# MITCH_2021-0_SHIELD.net
KiCad netlist of a schematic drawn in EAGLE
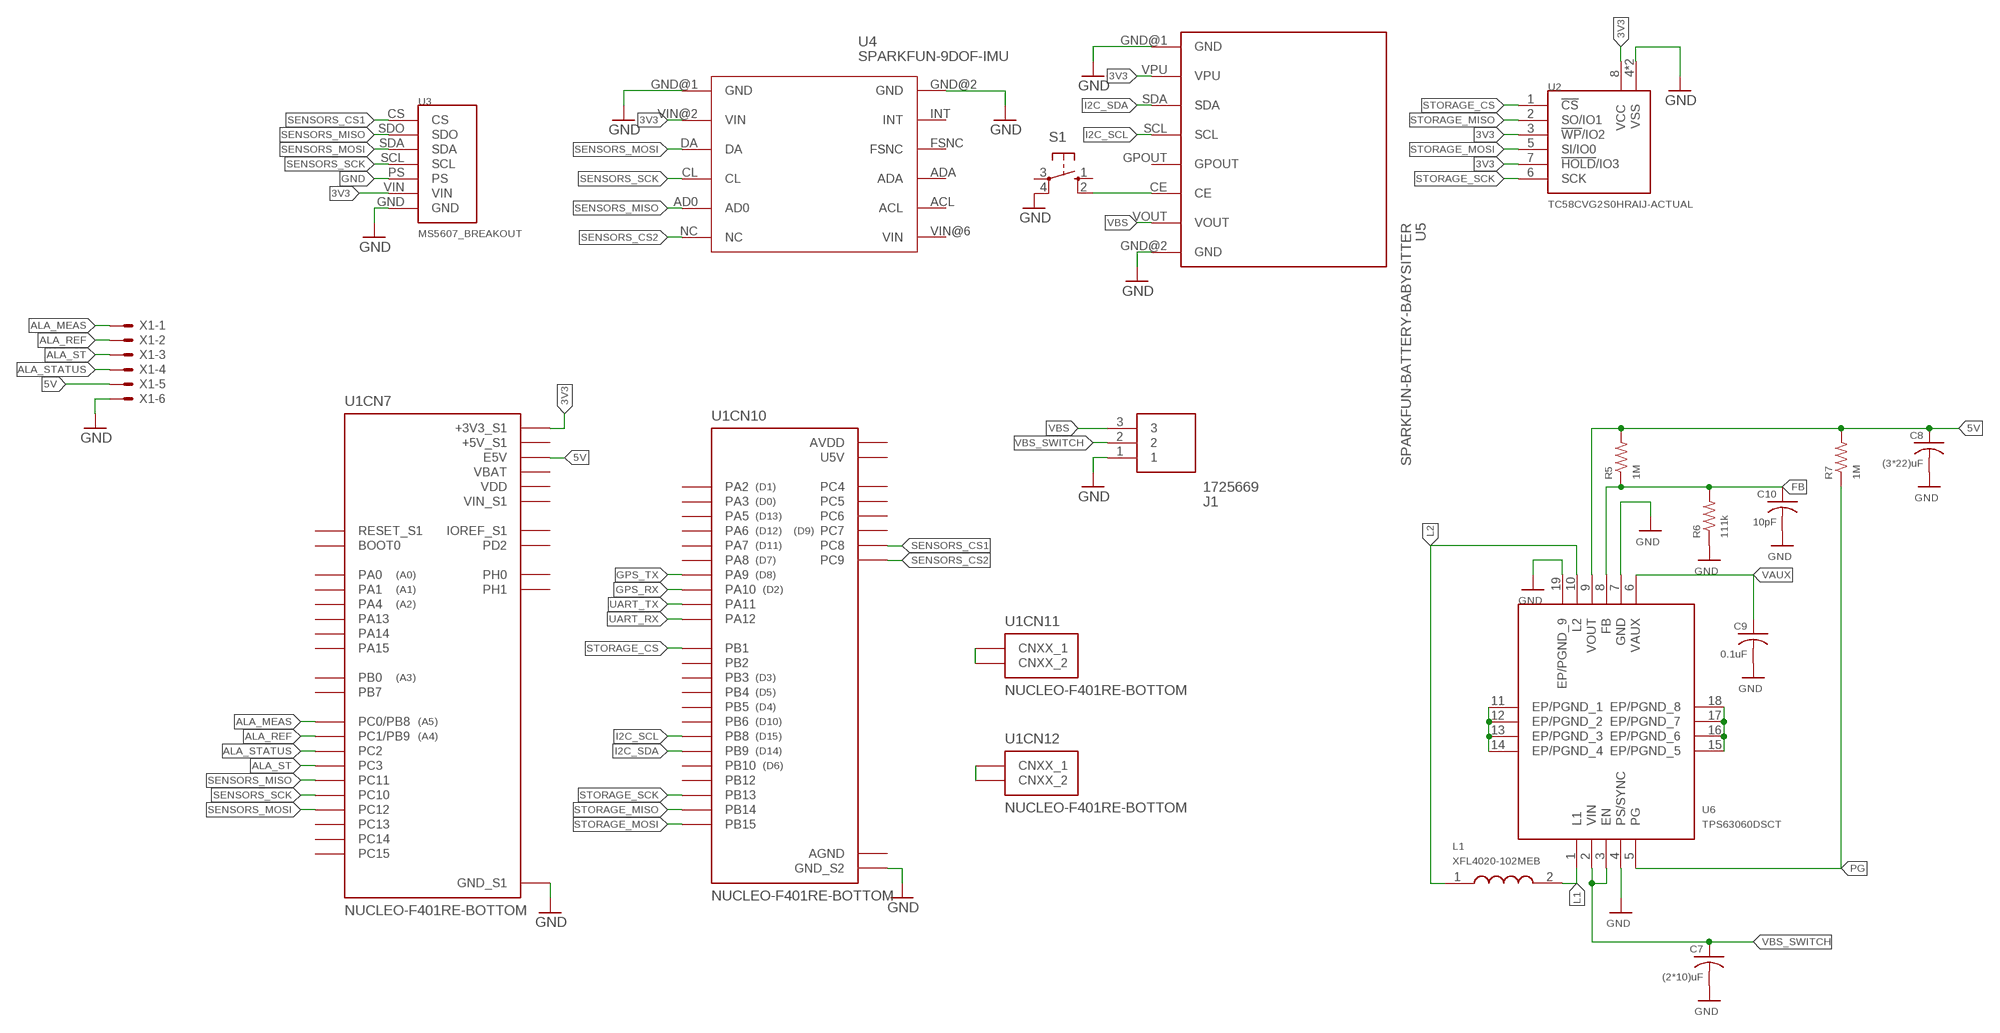
[diagram p0: schematic, sheet 1]

(export (version "E")
  (design (tool "Eeschema 10.0.6"))
  (components
    (comp (ref "C7")
      (value "(2*10)uF")
      (footprint "eagle-import:C0805")
      (libsource (lib "eagle-import") (part "C-USC0805"))
    )
    (comp (ref "C8")
      (value "(3*22)uF")
      (footprint "eagle-import:C0805")
      (libsource (lib "eagle-import") (part "C-USC0805"))
    )
    (comp (ref "C9")
      (value "0.1uF")
      (footprint "eagle-import:C0805")
      (libsource (lib "eagle-import") (part "C-USC0805"))
    )
    (comp (ref "C10")
      (value "10pF")
      (footprint "eagle-import:C0805")
      (libsource (lib "eagle-import") (part "C-USC0805"))
    )
    (comp (ref "J1")
      (value "1725669")
      (footprint "eagle-import:1725669")
      (fields (field (name "MOUSER_PART_NUMBER") "651-1725669"))
      (libsource (lib "eagle-import") (part "1725669"))
    )
    (comp (ref "L1")
      (value "XFL4020-102MEB")
      (footprint "eagle-import:XFL4020102MEB")
      (fields (field (name "MOUSER_PART_NUMBER") "994-XFL4020-102MEB"))
      (libsource (lib "eagle-import") (part "XFL4020-102MEB"))
    )
    (comp (ref "R5")
      (value "1M")
      (footprint "eagle-import:R0805")
      (libsource (lib "eagle-import") (part "R-US_R0805"))
    )
    (comp (ref "R6")
      (value "111k")
      (footprint "eagle-import:R0805")
      (libsource (lib "eagle-import") (part "R-US_R0805"))
    )
    (comp (ref "R7")
      (value "1M")
      (footprint "eagle-import:R0805")
      (libsource (lib "eagle-import") (part "R-US_R0805"))
    )
    (comp (ref "S1")
      (value "10-XX")
      (footprint "eagle-import:B3F-10XX")
      (fields (field (name "MPN") "B3F-1000"))
      (libsource (lib "eagle-import") (part "10-XX"))
    )
    (comp (ref "U1")
      (value "NUCLEO-F401RE-BOTTOM")
      (footprint "eagle-import:ST_NUCLEO-F401RE_BOTTOM")
      (fields (field (name "MF") "STMicroelectronics") (field (name "MP") "NUCLEO-F401RE"))
      (libsource (lib "eagle-import") (part "NUCLEO-F401RE-BOTTOM"))
    )
    (comp (ref "U2")
      (value "TC58CVG2S0HRAIJ-ACTUAL")
      (footprint "eagle-import:COMPUTER2_SON127P800X600X80-9T350X440N")
      (libsource (lib "eagle-import") (part "TC58CVG2S0HRAIJ-ACTUAL"))
    )
    (comp (ref "U3")
      (value "MS5607_BREAKOUT")
      (footprint "eagle-import:MS5607_BREAKOUT")
      (libsource (lib "eagle-import") (part "MS5607_BREAKOUT"))
    )
    (comp (ref "U4")
      (value "SPARKFUN-9DOF-IMU")
      (footprint "eagle-import:SPARKFUN-9DOF-IMU1")
      (libsource (lib "eagle-import") (part "SPARKFUN-9DOF-IMU"))
    )
    (comp (ref "U5")
      (value "SPARKFUN-BATTERY-BABYSITTER")
      (footprint "eagle-import:SPARKFUN-BATTERY-BABYSITTER")
      (libsource (lib "eagle-import") (part "SPARKFUN-BATTERY-BABYSITTER"))
    )
    (comp (ref "U6")
      (value "TPS63060DSCT")
      (footprint "eagle-import:TPS63060DSCT")
      (fields (field (name "MOUSER_PART_NUMBER") "595-TPS63060DSCT"))
      (libsource (lib "eagle-import") (part "TPS63060DSCT"))
    )
    (comp (ref "X1")
      (value "22-23-2061")
      (footprint "eagle-import:22-23-2061")
      (fields (field (name "MF") "MOLEX"))
      (libsource (lib "eagle-import") (part "22-23-2061"))
    )
  )
  (nets
    (net (code "1") (name "/+5V_S1") (class "Default")
      (node (ref "U1") (pin "CN7_18") (pinfunction "+5V_S1_CN7_18") (pintype "power_in"))
    )
    (net (code "2") (name "/AGND") (class "Default")
      (node (ref "U1") (pin "CN10_32") (pinfunction "AGND_CN10_32") (pintype "power_in"))
    )
    (net (code "3") (name "/AVDD") (class "Default")
      (node (ref "U1") (pin "CN10_7") (pinfunction "AVDD_CN10_7") (pintype "power_in"))
    )
    (net (code "4") (name "/U5V") (class "Default")
      (node (ref "U1") (pin "CN10_8") (pinfunction "U5V_CN10_8") (pintype "power_in"))
    )
    (net (code "5") (name "/VBAT") (class "Default")
      (node (ref "U1") (pin "CN7_33") (pinfunction "VBAT_CN7_33") (pintype "power_in"))
    )
    (net (code "6") (name "/VDD") (class "Default")
      (node (ref "U1") (pin "CN7_5") (pinfunction "VDD_CN7_5") (pintype "power_in"))
    )
    (net (code "7") (name "/VIN_S1") (class "Default")
      (node (ref "U1") (pin "CN7_24") (pinfunction "VIN_S1_CN7_24") (pintype "power_in"))
    )
    (net (code "8") (name "3V3") (class "Default")
      (node (ref "U1") (pin "CN7_16") (pinfunction "+3V3_S1_CN7_16") (pintype "power_in"))
      (node (ref "U2") (pin "3") (pinfunction "~{WP}/IO2_3") (pintype "bidirectional"))
      (node (ref "U2") (pin "7") (pinfunction "~{HOLD}/IO3_7") (pintype "bidirectional"))
      (node (ref "U2") (pin "8") (pinfunction "VCC_8") (pintype "bidirectional"))
      (node (ref "U3") (pin "VIN") (pinfunction "VIN_VIN") (pintype "bidirectional"))
      (node (ref "U4") (pin "VIN@2") (pinfunction "VIN_VIN@2") (pintype "bidirectional"))
      (node (ref "U5") (pin "VPU") (pinfunction "VPU_VPU") (pintype "bidirectional"))
    )
    (net (code "9") (name "5V") (class "Default")
      (node (ref "C8") (pin "1") (pinfunction "1_1") (pintype "passive"))
      (node (ref "R5") (pin "2") (pinfunction "2_2") (pintype "passive"))
      (node (ref "R7") (pin "2") (pinfunction "2_2") (pintype "passive"))
      (node (ref "U1") (pin "CN7_6") (pinfunction "E5V_CN7_6") (pintype "power_in"))
      (node (ref "U6") (pin "9") (pinfunction "VOUT_9") (pintype "bidirectional"))
      (node (ref "X1") (pin "5") (pinfunction "S_5") (pintype "passive"))
    )
    (net (code "10") (name "ALA_MEAS") (class "Default")
      (node (ref "U1") (pin "CN7_38") (pinfunction "PC0/PB8_CN7_38") (pintype "bidirectional"))
      (node (ref "X1") (pin "1") (pinfunction "S_1") (pintype "passive"))
    )
    (net (code "11") (name "ALA_REF") (class "Default")
      (node (ref "U1") (pin "CN7_36") (pinfunction "PC1/PB9_CN7_36") (pintype "bidirectional"))
      (node (ref "X1") (pin "2") (pinfunction "S_2") (pintype "passive"))
    )
    (net (code "12") (name "ALA_ST") (class "Default")
      (node (ref "U1") (pin "CN7_37") (pinfunction "PC3_CN7_37") (pintype "bidirectional"))
      (node (ref "X1") (pin "3") (pinfunction "S_3") (pintype "passive"))
    )
    (net (code "13") (name "ALA_STATUS") (class "Default")
      (node (ref "U1") (pin "CN7_35") (pinfunction "PC2_CN7_35") (pintype "bidirectional"))
      (node (ref "X1") (pin "4") (pinfunction "S_4") (pintype "passive"))
    )
    (net (code "14") (name "FB") (class "Default")
      (node (ref "C10") (pin "1") (pinfunction "1_1") (pintype "passive"))
      (node (ref "R5") (pin "1") (pinfunction "1_1") (pintype "passive"))
      (node (ref "R6") (pin "2") (pinfunction "2_2") (pintype "passive"))
      (node (ref "U6") (pin "8") (pinfunction "FB_8") (pintype "bidirectional"))
    )
    (net (code "15") (name "GND") (class "Default")
      (node (ref "C10") (pin "2") (pinfunction "2_2") (pintype "passive"))
      (node (ref "C7") (pin "2") (pinfunction "2_2") (pintype "passive"))
      (node (ref "C8") (pin "2") (pinfunction "2_2") (pintype "passive"))
      (node (ref "C9") (pin "2") (pinfunction "2_2") (pintype "passive"))
      (node (ref "J1") (pin "1") (pinfunction "1_1") (pintype "bidirectional"))
      (node (ref "R6") (pin "1") (pinfunction "1_1") (pintype "passive"))
      (node (ref "S1") (pin "4") (pinfunction "P1_4") (pintype "passive"))
      (node (ref "U1") (pin "CN10_20") (pinfunction "GND_S2_CN10_20") (pintype "power_in"))
      (node (ref "U1") (pin "CN10_9") (pinfunction "GND_S2_CN10_9") (pintype "power_in"))
      (node (ref "U1") (pin "CN7_19") (pinfunction "GND_S1_CN7_19") (pintype "power_in"))
      (node (ref "U1") (pin "CN7_20") (pinfunction "GND_S1_CN7_20") (pintype "power_in"))
      (node (ref "U1") (pin "CN7_22") (pinfunction "GND_S1_CN7_22") (pintype "power_in"))
      (node (ref "U1") (pin "CN7_8") (pinfunction "GND_S1_CN7_8") (pintype "power_in"))
      (node (ref "U2") (pin "4") (pinfunction "VSS_4") (pintype "bidirectional"))
      (node (ref "U2") (pin "9") (pinfunction "VSS_9") (pintype "bidirectional"))
      (node (ref "U3") (pin "GND") (pinfunction "GND_GND") (pintype "bidirectional"))
      (node (ref "U3") (pin "PS") (pinfunction "PS_PS") (pintype "bidirectional"))
      (node (ref "U4") (pin "GND@1") (pinfunction "GND_GND@1") (pintype "bidirectional"))
      (node (ref "U4") (pin "GND@2") (pinfunction "GND_GND@2") (pintype "bidirectional"))
      (node (ref "U5") (pin "GND@1") (pinfunction "GND_GND@1") (pintype "bidirectional"))
      (node (ref "U5") (pin "GND@2") (pinfunction "GND_GND@2") (pintype "bidirectional"))
      (node (ref "U6") (pin "11") (pinfunction "EP/PGND_1_11") (pintype "bidirectional"))
      (node (ref "U6") (pin "12") (pinfunction "EP/PGND_2_12") (pintype "bidirectional"))
      (node (ref "U6") (pin "13") (pinfunction "EP/PGND_3_13") (pintype "bidirectional"))
      (node (ref "U6") (pin "14") (pinfunction "EP/PGND_4_14") (pintype "bidirectional"))
      (node (ref "U6") (pin "15") (pinfunction "EP/PGND_5_15") (pintype "bidirectional"))
      (node (ref "U6") (pin "16") (pinfunction "EP/PGND_6_16") (pintype "bidirectional"))
      (node (ref "U6") (pin "17") (pinfunction "EP/PGND_7_17") (pintype "bidirectional"))
      (node (ref "U6") (pin "18") (pinfunction "EP/PGND_8_18") (pintype "bidirectional"))
      (node (ref "U6") (pin "19") (pinfunction "EP/PGND_9_19") (pintype "bidirectional"))
      (node (ref "U6") (pin "4") (pinfunction "PS/SYNC_4") (pintype "bidirectional"))
      (node (ref "U6") (pin "7") (pinfunction "GND_7") (pintype "bidirectional"))
      (node (ref "X1") (pin "6") (pinfunction "S_6") (pintype "passive"))
    )
    (net (code "16") (name "GPS_RX") (class "Default")
      (node (ref "U1") (pin "CN10_33") (pinfunction "PA10_CN10_33") (pintype "bidirectional"))
    )
    (net (code "17") (name "GPS_TX") (class "Default")
      (node (ref "U1") (pin "CN10_21") (pinfunction "PA9_CN10_21") (pintype "bidirectional"))
    )
    (net (code "18") (name "I2C_SCL") (class "Default")
      (node (ref "U1") (pin "CN10_3") (pinfunction "PB8_CN10_3") (pintype "bidirectional"))
      (node (ref "U5") (pin "SCL") (pinfunction "SCL_SCL") (pintype "bidirectional"))
    )
    (net (code "19") (name "I2C_SDA") (class "Default")
      (node (ref "U1") (pin "CN10_5") (pinfunction "PB9_CN10_5") (pintype "bidirectional"))
      (node (ref "U5") (pin "SDA") (pinfunction "SDA_SDA") (pintype "bidirectional"))
    )
    (net (code "20") (name "L1") (class "Default")
      (node (ref "L1") (pin "2") (pinfunction "2_2") (pintype "bidirectional"))
      (node (ref "U6") (pin "1") (pinfunction "L1_1") (pintype "bidirectional"))
    )
    (net (code "21") (name "L2") (class "Default")
      (node (ref "L1") (pin "1") (pinfunction "1_1") (pintype "bidirectional"))
      (node (ref "U6") (pin "10") (pinfunction "L2_10") (pintype "bidirectional"))
    )
    (net (code "22") (name "Net-(S1-S1)") (class "Default")
      (node (ref "S1") (pin "2") (pinfunction "S1_2") (pintype "passive"))
      (node (ref "U5") (pin "CE") (pinfunction "CE_CE") (pintype "bidirectional"))
    )
    (net (code "23") (name "Net-(U1B-CNXX_1)") (class "Default")
      (node (ref "U1") (pin "CN11_1") (pinfunction "CNXX_1_CN11_1") (pintype "input"))
      (node (ref "U1") (pin "CN11_2") (pinfunction "CNXX_2_CN11_2") (pintype "input"))
    )
    (net (code "24") (name "Net-(U1C-CNXX_1)") (class "Default")
      (node (ref "U1") (pin "CN12_1") (pinfunction "CNXX_1_CN12_1") (pintype "input"))
      (node (ref "U1") (pin "CN12_2") (pinfunction "CNXX_2_CN12_2") (pintype "input"))
    )
    (net (code "25") (name "PG") (class "Default")
      (node (ref "R7") (pin "1") (pinfunction "1_1") (pintype "passive"))
      (node (ref "U6") (pin "5") (pinfunction "PG_5") (pintype "bidirectional"))
    )
    (net (code "26") (name "SENSORS_CS1") (class "Default")
      (node (ref "U1") (pin "CN10_2") (pinfunction "PC8_CN10_2") (pintype "bidirectional"))
      (node (ref "U3") (pin "CS") (pinfunction "CS_CS") (pintype "bidirectional"))
    )
    (net (code "27") (name "SENSORS_CS2") (class "Default")
      (node (ref "U1") (pin "CN10_1") (pinfunction "PC9_CN10_1") (pintype "bidirectional"))
      (node (ref "U4") (pin "NC") (pinfunction "NC_NC") (pintype "bidirectional"))
    )
    (net (code "28") (name "SENSORS_MISO") (class "Default")
      (node (ref "U1") (pin "CN7_2") (pinfunction "PC11_CN7_2") (pintype "bidirectional"))
      (node (ref "U3") (pin "SDO") (pinfunction "SDO_SDO") (pintype "bidirectional"))
      (node (ref "U4") (pin "AD0") (pinfunction "AD0_AD0") (pintype "bidirectional"))
    )
    (net (code "29") (name "SENSORS_MOSI") (class "Default")
      (node (ref "U1") (pin "CN7_3") (pinfunction "PC12_CN7_3") (pintype "bidirectional"))
      (node (ref "U3") (pin "SDA") (pinfunction "SDA_SDA") (pintype "bidirectional"))
      (node (ref "U4") (pin "DA") (pinfunction "DA_DA") (pintype "bidirectional"))
    )
    (net (code "30") (name "SENSORS_SCK") (class "Default")
      (node (ref "U1") (pin "CN7_1") (pinfunction "PC10_CN7_1") (pintype "bidirectional"))
      (node (ref "U3") (pin "SCL") (pinfunction "SCL_SCL") (pintype "bidirectional"))
      (node (ref "U4") (pin "CL") (pinfunction "CL_CL") (pintype "bidirectional"))
    )
    (net (code "31") (name "STORAGE_CS") (class "Default")
      (node (ref "U1") (pin "CN10_24") (pinfunction "PB1_CN10_24") (pintype "bidirectional"))
      (node (ref "U2") (pin "1") (pinfunction "~{CS}_1") (pintype "bidirectional"))
    )
    (net (code "32") (name "STORAGE_MISO") (class "Default")
      (node (ref "U1") (pin "CN10_28") (pinfunction "PB14_CN10_28") (pintype "bidirectional"))
      (node (ref "U2") (pin "2") (pinfunction "SO/IO1_2") (pintype "bidirectional"))
    )
    (net (code "33") (name "STORAGE_MOSI") (class "Default")
      (node (ref "U1") (pin "CN10_26") (pinfunction "PB15_CN10_26") (pintype "bidirectional"))
      (node (ref "U2") (pin "5") (pinfunction "SI/IO0_5") (pintype "bidirectional"))
    )
    (net (code "34") (name "STORAGE_SCK") (class "Default")
      (node (ref "U1") (pin "CN10_30") (pinfunction "PB13_CN10_30") (pintype "bidirectional"))
      (node (ref "U2") (pin "6") (pinfunction "SCK_6") (pintype "bidirectional"))
    )
    (net (code "35") (name "UART_RX") (class "Default")
      (node (ref "U1") (pin "CN10_12") (pinfunction "PA12_CN10_12") (pintype "bidirectional"))
    )
    (net (code "36") (name "UART_TX") (class "Default")
      (node (ref "U1") (pin "CN10_14") (pinfunction "PA11_CN10_14") (pintype "bidirectional"))
    )
    (net (code "37") (name "VAUX") (class "Default")
      (node (ref "C9") (pin "1") (pinfunction "1_1") (pintype "passive"))
      (node (ref "U6") (pin "6") (pinfunction "VAUX_6") (pintype "bidirectional"))
    )
    (net (code "38") (name "VBS") (class "Default")
      (node (ref "J1") (pin "3") (pinfunction "3_3") (pintype "bidirectional"))
      (node (ref "U5") (pin "VOUT") (pinfunction "VOUT_VOUT") (pintype "bidirectional"))
    )
    (net (code "39") (name "VBS_SWITCH") (class "Default")
      (node (ref "C7") (pin "1") (pinfunction "1_1") (pintype "passive"))
      (node (ref "J1") (pin "2") (pinfunction "2_2") (pintype "bidirectional"))
      (node (ref "U6") (pin "2") (pinfunction "VIN_2") (pintype "bidirectional"))
      (node (ref "U6") (pin "3") (pinfunction "EN_3") (pintype "bidirectional"))
    )
    (net (code "40") (name "unconnected-(S1-P-Pad3)") (class "Default")
      (node (ref "S1") (pin "3") (pinfunction "P_3") (pintype "passive"))
    )
    (net (code "41") (name "unconnected-(S1-S-Pad1)") (class "Default")
      (node (ref "S1") (pin "1") (pinfunction "S_1") (pintype "passive"))
    )
    (net (code "42") (name "unconnected-(U1A-PA2-PadCN10_35)") (class "Default")
      (node (ref "U1") (pin "CN10_35") (pinfunction "PA2_CN10_35") (pintype "bidirectional"))
    )
    (net (code "43") (name "unconnected-(U1A-PA3-PadCN10_37)") (class "Default")
      (node (ref "U1") (pin "CN10_37") (pinfunction "PA3_CN10_37") (pintype "bidirectional"))
    )
    (net (code "44") (name "unconnected-(U1A-PA5-PadCN10_11)") (class "Default")
      (node (ref "U1") (pin "CN10_11") (pinfunction "PA5_CN10_11") (pintype "bidirectional"))
    )
    (net (code "45") (name "unconnected-(U1A-PA6-PadCN10_13)") (class "Default")
      (node (ref "U1") (pin "CN10_13") (pinfunction "PA6_CN10_13") (pintype "bidirectional"))
    )
    (net (code "46") (name "unconnected-(U1A-PA7-PadCN10_15)") (class "Default")
      (node (ref "U1") (pin "CN10_15") (pinfunction "PA7_CN10_15") (pintype "bidirectional"))
    )
    (net (code "47") (name "unconnected-(U1A-PA8-PadCN10_23)") (class "Default")
      (node (ref "U1") (pin "CN10_23") (pinfunction "PA8_CN10_23") (pintype "bidirectional"))
    )
    (net (code "48") (name "unconnected-(U1A-PB2-PadCN10_22)") (class "Default")
      (node (ref "U1") (pin "CN10_22") (pinfunction "PB2_CN10_22") (pintype "bidirectional"))
    )
    (net (code "49") (name "unconnected-(U1A-PB3-PadCN10_31)") (class "Default")
      (node (ref "U1") (pin "CN10_31") (pinfunction "PB3_CN10_31") (pintype "bidirectional"))
    )
    (net (code "50") (name "unconnected-(U1A-PB4-PadCN10_27)") (class "Default")
      (node (ref "U1") (pin "CN10_27") (pinfunction "PB4_CN10_27") (pintype "bidirectional"))
    )
    (net (code "51") (name "unconnected-(U1A-PB5-PadCN10_29)") (class "Default")
      (node (ref "U1") (pin "CN10_29") (pinfunction "PB5_CN10_29") (pintype "bidirectional"))
    )
    (net (code "52") (name "unconnected-(U1A-PB6-PadCN10_17)") (class "Default")
      (node (ref "U1") (pin "CN10_17") (pinfunction "PB6_CN10_17") (pintype "bidirectional"))
    )
    (net (code "53") (name "unconnected-(U1A-PB10-PadCN10_25)") (class "Default")
      (node (ref "U1") (pin "CN10_25") (pinfunction "PB10_CN10_25") (pintype "bidirectional"))
    )
    (net (code "54") (name "unconnected-(U1A-PB12-PadCN10_16)") (class "Default")
      (node (ref "U1") (pin "CN10_16") (pinfunction "PB12_CN10_16") (pintype "bidirectional"))
    )
    (net (code "55") (name "unconnected-(U1A-PC4-PadCN10_34)") (class "Default")
      (node (ref "U1") (pin "CN10_34") (pinfunction "PC4_CN10_34") (pintype "bidirectional"))
    )
    (net (code "56") (name "unconnected-(U1A-PC5-PadCN10_6)") (class "Default")
      (node (ref "U1") (pin "CN10_6") (pinfunction "PC5_CN10_6") (pintype "bidirectional"))
    )
    (net (code "57") (name "unconnected-(U1A-PC6-PadCN10_4)") (class "Default")
      (node (ref "U1") (pin "CN10_4") (pinfunction "PC6_CN10_4") (pintype "bidirectional"))
    )
    (net (code "58") (name "unconnected-(U1A-PC7-PadCN10_19)") (class "Default")
      (node (ref "U1") (pin "CN10_19") (pinfunction "PC7_CN10_19") (pintype "bidirectional"))
    )
    (net (code "59") (name "unconnected-(U1D-BOOT0-PadCN7_7)") (class "Default")
      (node (ref "U1") (pin "CN7_7") (pinfunction "BOOT0_CN7_7") (pintype "bidirectional"))
    )
    (net (code "60") (name "unconnected-(U1D-IOREF_S1-PadCN7_12)") (class "Default")
      (node (ref "U1") (pin "CN7_12") (pinfunction "IOREF_S1_CN7_12") (pintype "bidirectional"))
    )
    (net (code "61") (name "unconnected-(U1D-PA0-PadCN7_28)") (class "Default")
      (node (ref "U1") (pin "CN7_28") (pinfunction "PA0_CN7_28") (pintype "bidirectional"))
    )
    (net (code "62") (name "unconnected-(U1D-PA1-PadCN7_30)") (class "Default")
      (node (ref "U1") (pin "CN7_30") (pinfunction "PA1_CN7_30") (pintype "bidirectional"))
    )
    (net (code "63") (name "unconnected-(U1D-PA4-PadCN7_32)") (class "Default")
      (node (ref "U1") (pin "CN7_32") (pinfunction "PA4_CN7_32") (pintype "bidirectional"))
    )
    (net (code "64") (name "unconnected-(U1D-PA13-PadCN7_13)") (class "Default")
      (node (ref "U1") (pin "CN7_13") (pinfunction "PA13_CN7_13") (pintype "bidirectional"))
    )
    (net (code "65") (name "unconnected-(U1D-PA14-PadCN7_15)") (class "Default")
      (node (ref "U1") (pin "CN7_15") (pinfunction "PA14_CN7_15") (pintype "bidirectional"))
    )
    (net (code "66") (name "unconnected-(U1D-PA15-PadCN7_17)") (class "Default")
      (node (ref "U1") (pin "CN7_17") (pinfunction "PA15_CN7_17") (pintype "bidirectional"))
    )
    (net (code "67") (name "unconnected-(U1D-PB0-PadCN7_34)") (class "Default")
      (node (ref "U1") (pin "CN7_34") (pinfunction "PB0_CN7_34") (pintype "bidirectional"))
    )
    (net (code "68") (name "unconnected-(U1D-PB7-PadCN7_21)") (class "Default")
      (node (ref "U1") (pin "CN7_21") (pinfunction "PB7_CN7_21") (pintype "bidirectional"))
    )
    (net (code "69") (name "unconnected-(U1D-PC13-PadCN7_23)") (class "Default")
      (node (ref "U1") (pin "CN7_23") (pinfunction "PC13_CN7_23") (pintype "bidirectional"))
    )
    (net (code "70") (name "unconnected-(U1D-PC14-PadCN7_25)") (class "Default")
      (node (ref "U1") (pin "CN7_25") (pinfunction "PC14_CN7_25") (pintype "bidirectional"))
    )
    (net (code "71") (name "unconnected-(U1D-PC15-PadCN7_27)") (class "Default")
      (node (ref "U1") (pin "CN7_27") (pinfunction "PC15_CN7_27") (pintype "bidirectional"))
    )
    (net (code "72") (name "unconnected-(U1D-PD2-PadCN7_4)") (class "Default")
      (node (ref "U1") (pin "CN7_4") (pinfunction "PD2_CN7_4") (pintype "bidirectional"))
    )
    (net (code "73") (name "unconnected-(U1D-PH0-PadCN7_29)") (class "Default")
      (node (ref "U1") (pin "CN7_29") (pinfunction "PH0_CN7_29") (pintype "bidirectional"))
    )
    (net (code "74") (name "unconnected-(U1D-PH1-PadCN7_31)") (class "Default")
      (node (ref "U1") (pin "CN7_31") (pinfunction "PH1_CN7_31") (pintype "bidirectional"))
    )
    (net (code "75") (name "unconnected-(U1D-RESET_S1-PadCN7_14)") (class "Default")
      (node (ref "U1") (pin "CN7_14") (pinfunction "RESET_S1_CN7_14") (pintype "bidirectional"))
    )
    (net (code "76") (name "unconnected-(U4-PadACL)") (class "Default")
      (node (ref "U4") (pin "ACL") (pinfunction "ACL_ACL") (pintype "bidirectional"))
    )
    (net (code "77") (name "unconnected-(U4-PadADA)") (class "Default")
      (node (ref "U4") (pin "ADA") (pinfunction "ADA_ADA") (pintype "bidirectional"))
    )
    (net (code "78") (name "unconnected-(U4-PadFSNC)") (class "Default")
      (node (ref "U4") (pin "FSNC") (pinfunction "FSNC_FSNC") (pintype "bidirectional"))
    )
    (net (code "79") (name "unconnected-(U4-PadINT)") (class "Default")
      (node (ref "U4") (pin "INT") (pinfunction "INT_INT") (pintype "bidirectional"))
    )
    (net (code "80") (name "unconnected-(U4-VIN-PadVIN@6)") (class "Default")
      (node (ref "U4") (pin "VIN@6") (pinfunction "VIN_VIN@6") (pintype "bidirectional"))
    )
    (net (code "81") (name "unconnected-(U5-PadGPOUT)") (class "Default")
      (node (ref "U5") (pin "GPOUT") (pinfunction "GPOUT_GPOUT") (pintype "bidirectional"))
    )
  )
)
